# NeuroDAC_Output_v1.net
KiCad netlist of a schematic drawn in EAGLE
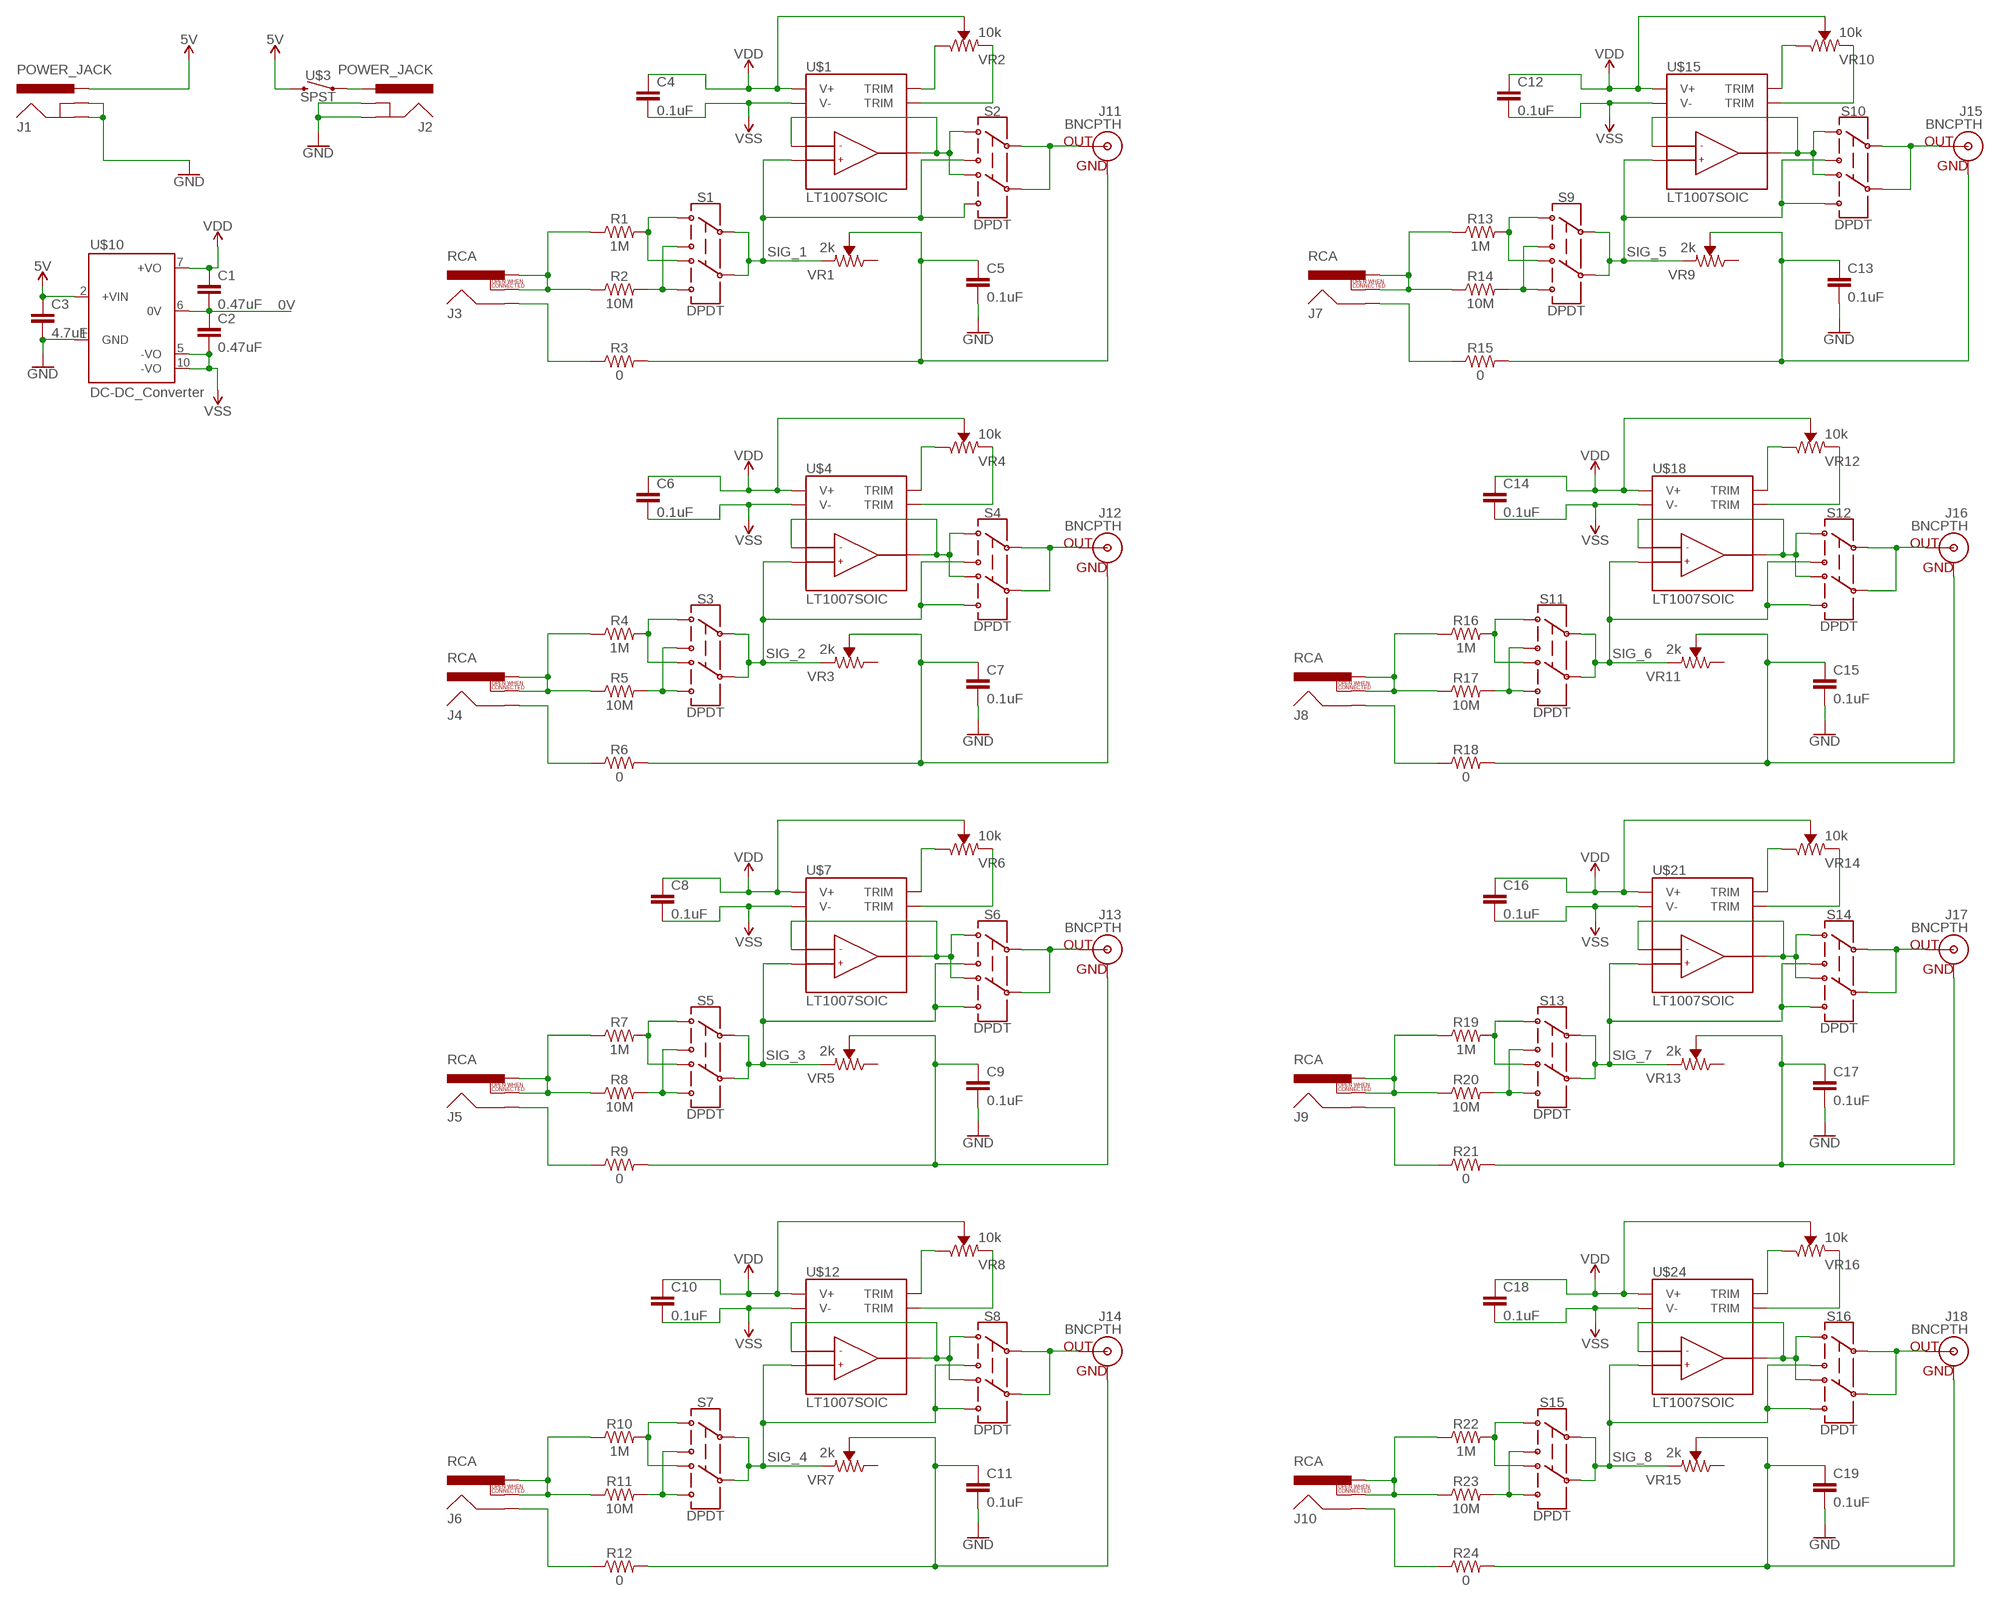
[diagram p0: schematic, sheet 1]

(export (version "E")
  (design (tool "Eeschema 10.0.6"))
  (components
    (comp (ref "C1")
      (value "0.47uF")
      (footprint "eagle-import:0603")
      (libsource (lib "eagle-import") (part "470NF-0603-25V-5%"))
    )
    (comp (ref "C2")
      (value "0.47uF")
      (footprint "eagle-import:0603")
      (libsource (lib "eagle-import") (part "470NF-0603-25V-5%"))
    )
    (comp (ref "C3")
      (value "4.7uF")
      (footprint "eagle-import:0805")
      (libsource (lib "eagle-import") (part "4.7UF-0805-25V-10%"))
    )
    (comp (ref "C4")
      (value "0.1uF")
      (footprint "eagle-import:0603")
      (libsource (lib "eagle-import") (part "0.1UF-0603-25V-5%"))
    )
    (comp (ref "C5")
      (value "0.1uF")
      (footprint "eagle-import:0603")
      (libsource (lib "eagle-import") (part "0.1UF-0603-25V-5%"))
    )
    (comp (ref "C6")
      (value "0.1uF")
      (footprint "eagle-import:0603")
      (libsource (lib "eagle-import") (part "0.1UF-0603-25V-5%"))
    )
    (comp (ref "C7")
      (value "0.1uF")
      (footprint "eagle-import:0603")
      (libsource (lib "eagle-import") (part "0.1UF-0603-25V-5%"))
    )
    (comp (ref "C8")
      (value "0.1uF")
      (footprint "eagle-import:0603")
      (libsource (lib "eagle-import") (part "0.1UF-0603-25V-5%"))
    )
    (comp (ref "C9")
      (value "0.1uF")
      (footprint "eagle-import:0603")
      (libsource (lib "eagle-import") (part "0.1UF-0603-25V-5%"))
    )
    (comp (ref "C10")
      (value "0.1uF")
      (footprint "eagle-import:0603")
      (libsource (lib "eagle-import") (part "0.1UF-0603-25V-5%"))
    )
    (comp (ref "C11")
      (value "0.1uF")
      (footprint "eagle-import:0603")
      (libsource (lib "eagle-import") (part "0.1UF-0603-25V-5%"))
    )
    (comp (ref "C12")
      (value "0.1uF")
      (footprint "eagle-import:0603")
      (libsource (lib "eagle-import") (part "0.1UF-0603-25V-5%"))
    )
    (comp (ref "C13")
      (value "0.1uF")
      (footprint "eagle-import:0603")
      (libsource (lib "eagle-import") (part "0.1UF-0603-25V-5%"))
    )
    (comp (ref "C14")
      (value "0.1uF")
      (footprint "eagle-import:0603")
      (libsource (lib "eagle-import") (part "0.1UF-0603-25V-5%"))
    )
    (comp (ref "C15")
      (value "0.1uF")
      (footprint "eagle-import:0603")
      (libsource (lib "eagle-import") (part "0.1UF-0603-25V-5%"))
    )
    (comp (ref "C16")
      (value "0.1uF")
      (footprint "eagle-import:0603")
      (libsource (lib "eagle-import") (part "0.1UF-0603-25V-5%"))
    )
    (comp (ref "C17")
      (value "0.1uF")
      (footprint "eagle-import:0603")
      (libsource (lib "eagle-import") (part "0.1UF-0603-25V-5%"))
    )
    (comp (ref "C18")
      (value "0.1uF")
      (footprint "eagle-import:0603")
      (libsource (lib "eagle-import") (part "0.1UF-0603-25V-5%"))
    )
    (comp (ref "C19")
      (value "0.1uF")
      (footprint "eagle-import:0603")
      (libsource (lib "eagle-import") (part "0.1UF-0603-25V-5%"))
    )
    (comp (ref "J1")
      (value "POWER_JACK")
      (footprint "eagle-import:POWER_JACK_PTH")
      (libsource (lib "eagle-import") (part "POWER_JACK"))
    )
    (comp (ref "J2")
      (value "POWER_JACK")
      (footprint "eagle-import:POWER_JACK_PTH")
      (libsource (lib "eagle-import") (part "POWER_JACK"))
    )
    (comp (ref "J3")
      (value "RCA")
      (footprint "eagle-import:RCA_LARGE_HOLE")
      (libsource (lib "eagle-import") (part "RCASWITCHCRAFT_LARGEHOLE"))
    )
    (comp (ref "J4")
      (value "RCA")
      (footprint "eagle-import:RCA_LARGE_HOLE")
      (libsource (lib "eagle-import") (part "RCASWITCHCRAFT_LARGEHOLE"))
    )
    (comp (ref "J5")
      (value "RCA")
      (footprint "eagle-import:RCA_LARGE_HOLE")
      (libsource (lib "eagle-import") (part "RCASWITCHCRAFT_LARGEHOLE"))
    )
    (comp (ref "J6")
      (value "RCA")
      (footprint "eagle-import:RCA_LARGE_HOLE")
      (libsource (lib "eagle-import") (part "RCASWITCHCRAFT_LARGEHOLE"))
    )
    (comp (ref "J7")
      (value "RCA")
      (footprint "eagle-import:RCA_LARGE_HOLE")
      (libsource (lib "eagle-import") (part "RCASWITCHCRAFT_LARGEHOLE"))
    )
    (comp (ref "J8")
      (value "RCA")
      (footprint "eagle-import:RCA_LARGE_HOLE")
      (libsource (lib "eagle-import") (part "RCASWITCHCRAFT_LARGEHOLE"))
    )
    (comp (ref "J9")
      (value "RCA")
      (footprint "eagle-import:RCA_LARGE_HOLE")
      (libsource (lib "eagle-import") (part "RCASWITCHCRAFT_LARGEHOLE"))
    )
    (comp (ref "J10")
      (value "RCA")
      (footprint "eagle-import:RCA_LARGE_HOLE")
      (libsource (lib "eagle-import") (part "RCASWITCHCRAFT_LARGEHOLE"))
    )
    (comp (ref "J11")
      (value "BNCPTH")
      (footprint "eagle-import:BNC")
      (libsource (lib "eagle-import") (part "BNCPTH"))
    )
    (comp (ref "J12")
      (value "BNCPTH")
      (footprint "eagle-import:BNC")
      (libsource (lib "eagle-import") (part "BNCPTH"))
    )
    (comp (ref "J13")
      (value "BNCPTH")
      (footprint "eagle-import:BNC")
      (libsource (lib "eagle-import") (part "BNCPTH"))
    )
    (comp (ref "J14")
      (value "BNCPTH")
      (footprint "eagle-import:BNC")
      (libsource (lib "eagle-import") (part "BNCPTH"))
    )
    (comp (ref "J15")
      (value "BNCPTH")
      (footprint "eagle-import:BNC")
      (libsource (lib "eagle-import") (part "BNCPTH"))
    )
    (comp (ref "J16")
      (value "BNCPTH")
      (footprint "eagle-import:BNC")
      (libsource (lib "eagle-import") (part "BNCPTH"))
    )
    (comp (ref "J17")
      (value "BNCPTH")
      (footprint "eagle-import:BNC")
      (libsource (lib "eagle-import") (part "BNCPTH"))
    )
    (comp (ref "J18")
      (value "BNCPTH")
      (footprint "eagle-import:BNC")
      (libsource (lib "eagle-import") (part "BNCPTH"))
    )
    (comp (ref "R1")
      (value "1M")
      (footprint "eagle-import:0603")
      (libsource (lib "eagle-import") (part "1MOHM-0603-1/4W-1%"))
    )
    (comp (ref "R2")
      (value "10M")
      (footprint "eagle-import:0603")
      (libsource (lib "eagle-import") (part "10MOHM-0603-1/4W-1%"))
    )
    (comp (ref "R3")
      (value "0")
      (footprint "eagle-import:0603")
      (libsource (lib "eagle-import") (part "0OHM-0603-1/4W"))
    )
    (comp (ref "R4")
      (value "1M")
      (footprint "eagle-import:0603")
      (libsource (lib "eagle-import") (part "1MOHM-0603-1/4W-1%"))
    )
    (comp (ref "R5")
      (value "10M")
      (footprint "eagle-import:0603")
      (libsource (lib "eagle-import") (part "10MOHM-0603-1/4W-1%"))
    )
    (comp (ref "R6")
      (value "0")
      (footprint "eagle-import:0603")
      (libsource (lib "eagle-import") (part "0OHM-0603-1/4W"))
    )
    (comp (ref "R7")
      (value "1M")
      (footprint "eagle-import:0603")
      (libsource (lib "eagle-import") (part "1MOHM-0603-1/4W-1%"))
    )
    (comp (ref "R8")
      (value "10M")
      (footprint "eagle-import:0603")
      (libsource (lib "eagle-import") (part "10MOHM-0603-1/4W-1%"))
    )
    (comp (ref "R9")
      (value "0")
      (footprint "eagle-import:0603")
      (libsource (lib "eagle-import") (part "0OHM-0603-1/4W"))
    )
    (comp (ref "R10")
      (value "1M")
      (footprint "eagle-import:0603")
      (libsource (lib "eagle-import") (part "1MOHM-0603-1/4W-1%"))
    )
    (comp (ref "R11")
      (value "10M")
      (footprint "eagle-import:0603")
      (libsource (lib "eagle-import") (part "10MOHM-0603-1/4W-1%"))
    )
    (comp (ref "R12")
      (value "0")
      (footprint "eagle-import:0603")
      (libsource (lib "eagle-import") (part "0OHM-0603-1/4W"))
    )
    (comp (ref "R13")
      (value "1M")
      (footprint "eagle-import:0603")
      (libsource (lib "eagle-import") (part "1MOHM-0603-1/4W-1%"))
    )
    (comp (ref "R14")
      (value "10M")
      (footprint "eagle-import:0603")
      (libsource (lib "eagle-import") (part "10MOHM-0603-1/4W-1%"))
    )
    (comp (ref "R15")
      (value "0")
      (footprint "eagle-import:0603")
      (libsource (lib "eagle-import") (part "0OHM-0603-1/4W"))
    )
    (comp (ref "R16")
      (value "1M")
      (footprint "eagle-import:0603")
      (libsource (lib "eagle-import") (part "1MOHM-0603-1/4W-1%"))
    )
    (comp (ref "R17")
      (value "10M")
      (footprint "eagle-import:0603")
      (libsource (lib "eagle-import") (part "10MOHM-0603-1/4W-1%"))
    )
    (comp (ref "R18")
      (value "0")
      (footprint "eagle-import:0603")
      (libsource (lib "eagle-import") (part "0OHM-0603-1/4W"))
    )
    (comp (ref "R19")
      (value "1M")
      (footprint "eagle-import:0603")
      (libsource (lib "eagle-import") (part "1MOHM-0603-1/4W-1%"))
    )
    (comp (ref "R20")
      (value "10M")
      (footprint "eagle-import:0603")
      (libsource (lib "eagle-import") (part "10MOHM-0603-1/4W-1%"))
    )
    (comp (ref "R21")
      (value "0")
      (footprint "eagle-import:0603")
      (libsource (lib "eagle-import") (part "0OHM-0603-1/4W"))
    )
    (comp (ref "R22")
      (value "1M")
      (footprint "eagle-import:0603")
      (libsource (lib "eagle-import") (part "1MOHM-0603-1/4W-1%"))
    )
    (comp (ref "R23")
      (value "10M")
      (footprint "eagle-import:0603")
      (libsource (lib "eagle-import") (part "10MOHM-0603-1/4W-1%"))
    )
    (comp (ref "R24")
      (value "0")
      (footprint "eagle-import:0603")
      (libsource (lib "eagle-import") (part "0OHM-0603-1/4W"))
    )
    (comp (ref "S1")
      (value "DPDT")
      (footprint "eagle-import:SWITCH_DPDT_JS202011SCQN")
      (libsource (lib "eagle-import") (part "SWITCH-DPDT-SMD-JS202011SCQN"))
    )
    (comp (ref "S2")
      (value "DPDT")
      (footprint "eagle-import:SWITCH_DPDT_JS202011SCQN")
      (libsource (lib "eagle-import") (part "SWITCH-DPDT-SMD-JS202011SCQN"))
    )
    (comp (ref "S3")
      (value "DPDT")
      (footprint "eagle-import:SWITCH_DPDT_JS202011SCQN")
      (libsource (lib "eagle-import") (part "SWITCH-DPDT-SMD-JS202011SCQN"))
    )
    (comp (ref "S4")
      (value "DPDT")
      (footprint "eagle-import:SWITCH_DPDT_JS202011SCQN")
      (libsource (lib "eagle-import") (part "SWITCH-DPDT-SMD-JS202011SCQN"))
    )
    (comp (ref "S5")
      (value "DPDT")
      (footprint "eagle-import:SWITCH_DPDT_JS202011SCQN")
      (libsource (lib "eagle-import") (part "SWITCH-DPDT-SMD-JS202011SCQN"))
    )
    (comp (ref "S6")
      (value "DPDT")
      (footprint "eagle-import:SWITCH_DPDT_JS202011SCQN")
      (libsource (lib "eagle-import") (part "SWITCH-DPDT-SMD-JS202011SCQN"))
    )
    (comp (ref "S7")
      (value "DPDT")
      (footprint "eagle-import:SWITCH_DPDT_JS202011SCQN")
      (libsource (lib "eagle-import") (part "SWITCH-DPDT-SMD-JS202011SCQN"))
    )
    (comp (ref "S8")
      (value "DPDT")
      (footprint "eagle-import:SWITCH_DPDT_JS202011SCQN")
      (libsource (lib "eagle-import") (part "SWITCH-DPDT-SMD-JS202011SCQN"))
    )
    (comp (ref "S9")
      (value "DPDT")
      (footprint "eagle-import:SWITCH_DPDT_JS202011SCQN")
      (libsource (lib "eagle-import") (part "SWITCH-DPDT-SMD-JS202011SCQN"))
    )
    (comp (ref "S10")
      (value "DPDT")
      (footprint "eagle-import:SWITCH_DPDT_JS202011SCQN")
      (libsource (lib "eagle-import") (part "SWITCH-DPDT-SMD-JS202011SCQN"))
    )
    (comp (ref "S11")
      (value "DPDT")
      (footprint "eagle-import:SWITCH_DPDT_JS202011SCQN")
      (libsource (lib "eagle-import") (part "SWITCH-DPDT-SMD-JS202011SCQN"))
    )
    (comp (ref "S12")
      (value "DPDT")
      (footprint "eagle-import:SWITCH_DPDT_JS202011SCQN")
      (libsource (lib "eagle-import") (part "SWITCH-DPDT-SMD-JS202011SCQN"))
    )
    (comp (ref "S13")
      (value "DPDT")
      (footprint "eagle-import:SWITCH_DPDT_JS202011SCQN")
      (libsource (lib "eagle-import") (part "SWITCH-DPDT-SMD-JS202011SCQN"))
    )
    (comp (ref "S14")
      (value "DPDT")
      (footprint "eagle-import:SWITCH_DPDT_JS202011SCQN")
      (libsource (lib "eagle-import") (part "SWITCH-DPDT-SMD-JS202011SCQN"))
    )
    (comp (ref "S15")
      (value "DPDT")
      (footprint "eagle-import:SWITCH_DPDT_JS202011SCQN")
      (libsource (lib "eagle-import") (part "SWITCH-DPDT-SMD-JS202011SCQN"))
    )
    (comp (ref "S16")
      (value "DPDT")
      (footprint "eagle-import:SWITCH_DPDT_JS202011SCQN")
      (libsource (lib "eagle-import") (part "SWITCH-DPDT-SMD-JS202011SCQN"))
    )
    (comp (ref "U$1")
      (value "LT1007SOIC")
      (footprint "eagle-import:S8")
      (libsource (lib "eagle-import") (part "LT1007SOIC"))
    )
    (comp (ref "U$3")
      (value "SPST")
      (footprint "eagle-import:SWITCH_SPST_L101011MS02Q")
      (libsource (lib "eagle-import") (part "SWITCH-SPST-L101011MS02Q"))
    )
    (comp (ref "U$4")
      (value "LT1007SOIC")
      (footprint "eagle-import:S8")
      (libsource (lib "eagle-import") (part "LT1007SOIC"))
    )
    (comp (ref "U$7")
      (value "LT1007SOIC")
      (footprint "eagle-import:S8")
      (libsource (lib "eagle-import") (part "LT1007SOIC"))
    )
    (comp (ref "U$10")
      (value "DC-DC_Converter")
      (footprint "eagle-import:VAT2-SMT")
      (libsource (lib "eagle-import") (part "DC-DC-CONVERTER_DUALOUT-VAT2-S5-D15-SMT"))
    )
    (comp (ref "U$12")
      (value "LT1007SOIC")
      (footprint "eagle-import:S8")
      (libsource (lib "eagle-import") (part "LT1007SOIC"))
    )
    (comp (ref "U$15")
      (value "LT1007SOIC")
      (footprint "eagle-import:S8")
      (libsource (lib "eagle-import") (part "LT1007SOIC"))
    )
    (comp (ref "U$18")
      (value "LT1007SOIC")
      (footprint "eagle-import:S8")
      (libsource (lib "eagle-import") (part "LT1007SOIC"))
    )
    (comp (ref "U$21")
      (value "LT1007SOIC")
      (footprint "eagle-import:S8")
      (libsource (lib "eagle-import") (part "LT1007SOIC"))
    )
    (comp (ref "U$24")
      (value "LT1007SOIC")
      (footprint "eagle-import:S8")
      (libsource (lib "eagle-import") (part "LT1007SOIC"))
    )
    (comp (ref "VR1")
      (value "2k")
      (footprint "eagle-import:TRIMPOT-SMD-ST4EB")
      (libsource (lib "eagle-import") (part "TRIMPOT-SMD-ST-4EB"))
    )
    (comp (ref "VR2")
      (value "10k")
      (footprint "eagle-import:TRIMPOT-SMD-ST4EB")
      (libsource (lib "eagle-import") (part "TRIMPOT-SMD-ST-4EB"))
    )
    (comp (ref "VR3")
      (value "2k")
      (footprint "eagle-import:TRIMPOT-SMD-ST4EB")
      (libsource (lib "eagle-import") (part "TRIMPOT-SMD-ST-4EB"))
    )
    (comp (ref "VR4")
      (value "10k")
      (footprint "eagle-import:TRIMPOT-SMD-ST4EB")
      (libsource (lib "eagle-import") (part "TRIMPOT-SMD-ST-4EB"))
    )
    (comp (ref "VR5")
      (value "2k")
      (footprint "eagle-import:TRIMPOT-SMD-ST4EB")
      (libsource (lib "eagle-import") (part "TRIMPOT-SMD-ST-4EB"))
    )
    (comp (ref "VR6")
      (value "10k")
      (footprint "eagle-import:TRIMPOT-SMD-ST4EB")
      (libsource (lib "eagle-import") (part "TRIMPOT-SMD-ST-4EB"))
    )
    (comp (ref "VR7")
      (value "2k")
      (footprint "eagle-import:TRIMPOT-SMD-ST4EB")
      (libsource (lib "eagle-import") (part "TRIMPOT-SMD-ST-4EB"))
    )
    (comp (ref "VR8")
      (value "10k")
      (footprint "eagle-import:TRIMPOT-SMD-ST4EB")
      (libsource (lib "eagle-import") (part "TRIMPOT-SMD-ST-4EB"))
    )
    (comp (ref "VR9")
      (value "2k")
      (footprint "eagle-import:TRIMPOT-SMD-ST4EB")
      (libsource (lib "eagle-import") (part "TRIMPOT-SMD-ST-4EB"))
    )
    (comp (ref "VR10")
      (value "10k")
      (footprint "eagle-import:TRIMPOT-SMD-ST4EB")
      (libsource (lib "eagle-import") (part "TRIMPOT-SMD-ST-4EB"))
    )
    (comp (ref "VR11")
      (value "2k")
      (footprint "eagle-import:TRIMPOT-SMD-ST4EB")
      (libsource (lib "eagle-import") (part "TRIMPOT-SMD-ST-4EB"))
    )
    (comp (ref "VR12")
      (value "10k")
      (footprint "eagle-import:TRIMPOT-SMD-ST4EB")
      (libsource (lib "eagle-import") (part "TRIMPOT-SMD-ST-4EB"))
    )
    (comp (ref "VR13")
      (value "2k")
      (footprint "eagle-import:TRIMPOT-SMD-ST4EB")
      (libsource (lib "eagle-import") (part "TRIMPOT-SMD-ST-4EB"))
    )
    (comp (ref "VR14")
      (value "10k")
      (footprint "eagle-import:TRIMPOT-SMD-ST4EB")
      (libsource (lib "eagle-import") (part "TRIMPOT-SMD-ST-4EB"))
    )
    (comp (ref "VR15")
      (value "2k")
      (footprint "eagle-import:TRIMPOT-SMD-ST4EB")
      (libsource (lib "eagle-import") (part "TRIMPOT-SMD-ST-4EB"))
    )
    (comp (ref "VR16")
      (value "10k")
      (footprint "eagle-import:TRIMPOT-SMD-ST4EB")
      (libsource (lib "eagle-import") (part "TRIMPOT-SMD-ST-4EB"))
    )
  )
  (nets
    (net (code "1") (name "/0V") (class "Default")
      (node (ref "C1") (pin "2") (pinfunction "2_2") (pintype "passive"))
      (node (ref "C11") (pin "1") (pinfunction "1_1") (pintype "passive"))
      (node (ref "C13") (pin "1") (pinfunction "1_1") (pintype "passive"))
      (node (ref "C15") (pin "1") (pinfunction "1_1") (pintype "passive"))
      (node (ref "C17") (pin "1") (pinfunction "1_1") (pintype "passive"))
      (node (ref "C19") (pin "1") (pinfunction "1_1") (pintype "passive"))
      (node (ref "C2") (pin "1") (pinfunction "1_1") (pintype "passive"))
      (node (ref "C5") (pin "1") (pinfunction "1_1") (pintype "passive"))
      (node (ref "C7") (pin "1") (pinfunction "1_1") (pintype "passive"))
      (node (ref "C9") (pin "1") (pinfunction "1_1") (pintype "passive"))
      (node (ref "J11") (pin "GND") (pinfunction "GND_GND") (pintype "bidirectional"))
      (node (ref "J12") (pin "GND") (pinfunction "GND_GND") (pintype "bidirectional"))
      (node (ref "J13") (pin "GND") (pinfunction "GND_GND") (pintype "bidirectional"))
      (node (ref "J14") (pin "GND") (pinfunction "GND_GND") (pintype "bidirectional"))
      (node (ref "J15") (pin "GND") (pinfunction "GND_GND") (pintype "bidirectional"))
      (node (ref "J16") (pin "GND") (pinfunction "GND_GND") (pintype "bidirectional"))
      (node (ref "J17") (pin "GND") (pinfunction "GND_GND") (pintype "bidirectional"))
      (node (ref "J18") (pin "GND") (pinfunction "GND_GND") (pintype "bidirectional"))
      (node (ref "R12") (pin "2") (pinfunction "2_2") (pintype "passive"))
      (node (ref "R15") (pin "2") (pinfunction "2_2") (pintype "passive"))
      (node (ref "R18") (pin "2") (pinfunction "2_2") (pintype "passive"))
      (node (ref "R21") (pin "2") (pinfunction "2_2") (pintype "passive"))
      (node (ref "R24") (pin "2") (pinfunction "2_2") (pintype "passive"))
      (node (ref "R3") (pin "2") (pinfunction "2_2") (pintype "passive"))
      (node (ref "R6") (pin "2") (pinfunction "2_2") (pintype "passive"))
      (node (ref "R9") (pin "2") (pinfunction "2_2") (pintype "passive"))
      (node (ref "U$10") (pin "6") (pinfunction "0V_6") (pintype "power_in"))
      (node (ref "VR1") (pin "2") (pinfunction "WIPER_2") (pintype "passive"))
      (node (ref "VR11") (pin "2") (pinfunction "WIPER_2") (pintype "passive"))
      (node (ref "VR13") (pin "2") (pinfunction "WIPER_2") (pintype "passive"))
      (node (ref "VR15") (pin "2") (pinfunction "WIPER_2") (pintype "passive"))
      (node (ref "VR3") (pin "2") (pinfunction "WIPER_2") (pintype "passive"))
      (node (ref "VR5") (pin "2") (pinfunction "WIPER_2") (pintype "passive"))
      (node (ref "VR7") (pin "2") (pinfunction "WIPER_2") (pintype "passive"))
      (node (ref "VR9") (pin "2") (pinfunction "WIPER_2") (pintype "passive"))
    )
    (net (code "2") (name "/SIG_1") (class "Default")
      (node (ref "S1") (pin "2") (pinfunction "2_2") (pintype "bidirectional"))
      (node (ref "S1") (pin "5") (pinfunction "5_5") (pintype "bidirectional"))
      (node (ref "S2") (pin "3") (pinfunction "3_3") (pintype "bidirectional"))
      (node (ref "S2") (pin "6") (pinfunction "6_6") (pintype "bidirectional"))
      (node (ref "U$1") (pin "3") (pinfunction "IN+_3") (pintype "input"))
      (node (ref "VR1") (pin "1") (pinfunction "CCW_1") (pintype "passive"))
    )
    (net (code "3") (name "/SIG_2") (class "Default")
      (node (ref "S3") (pin "2") (pinfunction "2_2") (pintype "bidirectional"))
      (node (ref "S3") (pin "5") (pinfunction "5_5") (pintype "bidirectional"))
      (node (ref "S4") (pin "3") (pinfunction "3_3") (pintype "bidirectional"))
      (node (ref "S4") (pin "6") (pinfunction "6_6") (pintype "bidirectional"))
      (node (ref "U$4") (pin "3") (pinfunction "IN+_3") (pintype "input"))
      (node (ref "VR3") (pin "1") (pinfunction "CCW_1") (pintype "passive"))
    )
    (net (code "4") (name "/SIG_3") (class "Default")
      (node (ref "S5") (pin "2") (pinfunction "2_2") (pintype "bidirectional"))
      (node (ref "S5") (pin "5") (pinfunction "5_5") (pintype "bidirectional"))
      (node (ref "S6") (pin "3") (pinfunction "3_3") (pintype "bidirectional"))
      (node (ref "S6") (pin "6") (pinfunction "6_6") (pintype "bidirectional"))
      (node (ref "U$7") (pin "3") (pinfunction "IN+_3") (pintype "input"))
      (node (ref "VR5") (pin "1") (pinfunction "CCW_1") (pintype "passive"))
    )
    (net (code "5") (name "/SIG_4") (class "Default")
      (node (ref "S7") (pin "2") (pinfunction "2_2") (pintype "bidirectional"))
      (node (ref "S7") (pin "5") (pinfunction "5_5") (pintype "bidirectional"))
      (node (ref "S8") (pin "3") (pinfunction "3_3") (pintype "bidirectional"))
      (node (ref "S8") (pin "6") (pinfunction "6_6") (pintype "bidirectional"))
      (node (ref "U$12") (pin "3") (pinfunction "IN+_3") (pintype "input"))
      (node (ref "VR7") (pin "1") (pinfunction "CCW_1") (pintype "passive"))
    )
    (net (code "6") (name "/SIG_5") (class "Default")
      (node (ref "S10") (pin "3") (pinfunction "3_3") (pintype "bidirectional"))
      (node (ref "S10") (pin "6") (pinfunction "6_6") (pintype "bidirectional"))
      (node (ref "S9") (pin "2") (pinfunction "2_2") (pintype "bidirectional"))
      (node (ref "S9") (pin "5") (pinfunction "5_5") (pintype "bidirectional"))
      (node (ref "U$15") (pin "3") (pinfunction "IN+_3") (pintype "input"))
      (node (ref "VR9") (pin "1") (pinfunction "CCW_1") (pintype "passive"))
    )
    (net (code "7") (name "/SIG_6") (class "Default")
      (node (ref "S11") (pin "2") (pinfunction "2_2") (pintype "bidirectional"))
      (node (ref "S11") (pin "5") (pinfunction "5_5") (pintype "bidirectional"))
      (node (ref "S12") (pin "3") (pinfunction "3_3") (pintype "bidirectional"))
      (node (ref "S12") (pin "6") (pinfunction "6_6") (pintype "bidirectional"))
      (node (ref "U$18") (pin "3") (pinfunction "IN+_3") (pintype "input"))
      (node (ref "VR11") (pin "1") (pinfunction "CCW_1") (pintype "passive"))
    )
    (net (code "8") (name "/SIG_7") (class "Default")
      (node (ref "S13") (pin "2") (pinfunction "2_2") (pintype "bidirectional"))
      (node (ref "S13") (pin "5") (pinfunction "5_5") (pintype "bidirectional"))
      (node (ref "S14") (pin "3") (pinfunction "3_3") (pintype "bidirectional"))
      (node (ref "S14") (pin "6") (pinfunction "6_6") (pintype "bidirectional"))
      (node (ref "U$21") (pin "3") (pinfunction "IN+_3") (pintype "input"))
      (node (ref "VR13") (pin "1") (pinfunction "CCW_1") (pintype "passive"))
    )
    (net (code "9") (name "/SIG_8") (class "Default")
      (node (ref "S15") (pin "2") (pinfunction "2_2") (pintype "bidirectional"))
      (node (ref "S15") (pin "5") (pinfunction "5_5") (pintype "bidirectional"))
      (node (ref "S16") (pin "3") (pinfunction "3_3") (pintype "bidirectional"))
      (node (ref "S16") (pin "6") (pinfunction "6_6") (pintype "bidirectional"))
      (node (ref "U$24") (pin "3") (pinfunction "IN+_3") (pintype "input"))
      (node (ref "VR15") (pin "1") (pinfunction "CCW_1") (pintype "passive"))
    )
    (net (code "10") (name "5V") (class "Default")
      (node (ref "C3") (pin "1") (pinfunction "1_1") (pintype "passive"))
      (node (ref "J1") (pin "PWR") (pinfunction "PWR_PWR") (pintype "bidirectional"))
      (node (ref "U$10") (pin "2") (pinfunction "+VIN_2") (pintype "power_in"))
      (node (ref "U$3") (pin "2") (pinfunction "2_2") (pintype "passive"))
    )
    (net (code "11") (name "GND") (class "Default")
      (node (ref "C11") (pin "2") (pinfunction "2_2") (pintype "passive"))
      (node (ref "C13") (pin "2") (pinfunction "2_2") (pintype "passive"))
      (node (ref "C15") (pin "2") (pinfunction "2_2") (pintype "passive"))
      (node (ref "C17") (pin "2") (pinfunction "2_2") (pintype "passive"))
      (node (ref "C19") (pin "2") (pinfunction "2_2") (pintype "passive"))
      (node (ref "C3") (pin "2") (pinfunction "2_2") (pintype "passive"))
      (node (ref "C5") (pin "2") (pinfunction "2_2") (pintype "passive"))
      (node (ref "C7") (pin "2") (pinfunction "2_2") (pintype "passive"))
      (node (ref "C9") (pin "2") (pinfunction "2_2") (pintype "passive"))
      (node (ref "J1") (pin "GND") (pinfunction "GND_GND") (pintype "bidirectional"))
      (node (ref "J1") (pin "GNDBREAK") (pinfunction "GNDBREAK_GNDBREAK") (pintype "bidirectional"))
      (node (ref "J2") (pin "GND") (pinfunction "GND_GND") (pintype "bidirectional"))
      (node (ref "J2") (pin "GNDBREAK") (pinfunction "GNDBREAK_GNDBREAK") (pintype "bidirectional"))
      (node (ref "U$10") (pin "1") (pinfunction "GND_1") (pintype "power_in"))
    )
    (net (code "12") (name "Net-(J2-PadPWR)") (class "Default")
      (node (ref "J2") (pin "PWR") (pinfunction "PWR_PWR") (pintype "bidirectional"))
      (node (ref "U$3") (pin "1") (pinfunction "1_1") (pintype "passive"))
    )
    (net (code "13") (name "Net-(J3-PadPIN)") (class "Default")
      (node (ref "J3") (pin "PIN") (pinfunction "PIN_PIN") (pintype "bidirectional"))
      (node (ref "J3") (pin "SWITCH") (pinfunction "SWITCH_SWITCH") (pintype "bidirectional"))
      (node (ref "R1") (pin "1") (pinfunction "1_1") (pintype "passive"))
      (node (ref "R2") (pin "1") (pinfunction "1_1") (pintype "passive"))
    )
    (net (code "14") (name "Net-(J3-PadSHELL)") (class "Default")
      (node (ref "J3") (pin "SHELL") (pinfunction "SHELL_SHELL") (pintype "bidirectional"))
      (node (ref "R3") (pin "1") (pinfunction "1_1") (pintype "passive"))
    )
    (net (code "15") (name "Net-(J4-PadPIN)") (class "Default")
      (node (ref "J4") (pin "PIN") (pinfunction "PIN_PIN") (pintype "bidirectional"))
      (node (ref "J4") (pin "SWITCH") (pinfunction "SWITCH_SWITCH") (pintype "bidirectional"))
      (node (ref "R4") (pin "1") (pinfunction "1_1") (pintype "passive"))
      (node (ref "R5") (pin "1") (pinfunction "1_1") (pintype "passive"))
    )
    (net (code "16") (name "Net-(J4-PadSHELL)") (class "Default")
      (node (ref "J4") (pin "SHELL") (pinfunction "SHELL_SHELL") (pintype "bidirectional"))
      (node (ref "R6") (pin "1") (pinfunction "1_1") (pintype "passive"))
    )
    (net (code "17") (name "Net-(J5-PadPIN)") (class "Default")
      (node (ref "J5") (pin "PIN") (pinfunction "PIN_PIN") (pintype "bidirectional"))
      (node (ref "J5") (pin "SWITCH") (pinfunction "SWITCH_SWITCH") (pintype "bidirectional"))
      (node (ref "R7") (pin "1") (pinfunction "1_1") (pintype "passive"))
      (node (ref "R8") (pin "1") (pinfunction "1_1") (pintype "passive"))
    )
    (net (code "18") (name "Net-(J5-PadSHELL)") (class "Default")
      (node (ref "J5") (pin "SHELL") (pinfunction "SHELL_SHELL") (pintype "bidirectional"))
      (node (ref "R9") (pin "1") (pinfunction "1_1") (pintype "passive"))
    )
    (net (code "19") (name "Net-(J6-PadPIN)") (class "Default")
      (node (ref "J6") (pin "PIN") (pinfunction "PIN_PIN") (pintype "bidirectional"))
      (node (ref "J6") (pin "SWITCH") (pinfunction "SWITCH_SWITCH") (pintype "bidirectional"))
      (node (ref "R10") (pin "1") (pinfunction "1_1") (pintype "passive"))
      (node (ref "R11") (pin "1") (pinfunction "1_1") (pintype "passive"))
    )
    (net (code "20") (name "Net-(J6-PadSHELL)") (class "Default")
      (node (ref "J6") (pin "SHELL") (pinfunction "SHELL_SHELL") (pintype "bidirectional"))
      (node (ref "R12") (pin "1") (pinfunction "1_1") (pintype "passive"))
    )
    (net (code "21") (name "Net-(J7-PadPIN)") (class "Default")
      (node (ref "J7") (pin "PIN") (pinfunction "PIN_PIN") (pintype "bidirectional"))
      (node (ref "J7") (pin "SWITCH") (pinfunction "SWITCH_SWITCH") (pintype "bidirectional"))
      (node (ref "R13") (pin "1") (pinfunction "1_1") (pintype "passive"))
      (node (ref "R14") (pin "1") (pinfunction "1_1") (pintype "passive"))
    )
    (net (code "22") (name "Net-(J7-PadSHELL)") (class "Default")
      (node (ref "J7") (pin "SHELL") (pinfunction "SHELL_SHELL") (pintype "bidirectional"))
      (node (ref "R15") (pin "1") (pinfunction "1_1") (pintype "passive"))
    )
    (net (code "23") (name "Net-(J8-PadPIN)") (class "Default")
      (node (ref "J8") (pin "PIN") (pinfunction "PIN_PIN") (pintype "bidirectional"))
      (node (ref "J8") (pin "SWITCH") (pinfunction "SWITCH_SWITCH") (pintype "bidirectional"))
      (node (ref "R16") (pin "1") (pinfunction "1_1") (pintype "passive"))
      (node (ref "R17") (pin "1") (pinfunction "1_1") (pintype "passive"))
    )
    (net (code "24") (name "Net-(J8-PadSHELL)") (class "Default")
      (node (ref "J8") (pin "SHELL") (pinfunction "SHELL_SHELL") (pintype "bidirectional"))
      (node (ref "R18") (pin "1") (pinfunction "1_1") (pintype "passive"))
    )
    (net (code "25") (name "Net-(J9-PadPIN)") (class "Default")
      (node (ref "J9") (pin "PIN") (pinfunction "PIN_PIN") (pintype "bidirectional"))
      (node (ref "J9") (pin "SWITCH") (pinfunction "SWITCH_SWITCH") (pintype "bidirectional"))
      (node (ref "R19") (pin "1") (pinfunction "1_1") (pintype "passive"))
      (node (ref "R20") (pin "1") (pinfunction "1_1") (pintype "passive"))
    )
    (net (code "26") (name "Net-(J9-PadSHELL)") (class "Default")
      (node (ref "J9") (pin "SHELL") (pinfunction "SHELL_SHELL") (pintype "bidirectional"))
      (node (ref "R21") (pin "1") (pinfunction "1_1") (pintype "passive"))
    )
    (net (code "27") (name "Net-(J10-PadPIN)") (class "Default")
      (node (ref "J10") (pin "PIN") (pinfunction "PIN_PIN") (pintype "bidirectional"))
      (node (ref "J10") (pin "SWITCH") (pinfunction "SWITCH_SWITCH") (pintype "bidirectional"))
      (node (ref "R22") (pin "1") (pinfunction "1_1") (pintype "passive"))
      (node (ref "R23") (pin "1") (pinfunction "1_1") (pintype "passive"))
    )
    (net (code "28") (name "Net-(J10-PadSHELL)") (class "Default")
      (node (ref "J10") (pin "SHELL") (pinfunction "SHELL_SHELL") (pintype "bidirectional"))
      (node (ref "R24") (pin "1") (pinfunction "1_1") (pintype "passive"))
    )
    (net (code "29") (name "Net-(J11-OUT)") (class "Default")
      (node (ref "J11") (pin "S") (pinfunction "OUT_S") (pintype "bidirectional"))
      (node (ref "S2") (pin "2") (pinfunction "2_2") (pintype "bidirectional"))
      (node (ref "S2") (pin "5") (pinfunction "5_5") (pintype "bidirectional"))
    )
    (net (code "30") (name "Net-(J12-OUT)") (class "Default")
      (node (ref "J12") (pin "S") (pinfunction "OUT_S") (pintype "bidirectional"))
      (node (ref "S4") (pin "2") (pinfunction "2_2") (pintype "bidirectional"))
      (node (ref "S4") (pin "5") (pinfunction "5_5") (pintype "bidirectional"))
    )
    (net (code "31") (name "Net-(J13-OUT)") (class "Default")
      (node (ref "J13") (pin "S") (pinfunction "OUT_S") (pintype "bidirectional"))
      (node (ref "S6") (pin "2") (pinfunction "2_2") (pintype "bidirectional"))
      (node (ref "S6") (pin "5") (pinfunction "5_5") (pintype "bidirectional"))
    )
    (net (code "32") (name "Net-(J14-OUT)") (class "Default")
      (node (ref "J14") (pin "S") (pinfunction "OUT_S") (pintype "bidirectional"))
      (node (ref "S8") (pin "2") (pinfunction "2_2") (pintype "bidirectional"))
      (node (ref "S8") (pin "5") (pinfunction "5_5") (pintype "bidirectional"))
    )
    (net (code "33") (name "Net-(J15-OUT)") (class "Default")
      (node (ref "J15") (pin "S") (pinfunction "OUT_S") (pintype "bidirectional"))
      (node (ref "S10") (pin "2") (pinfunction "2_2") (pintype "bidirectional"))
      (node (ref "S10") (pin "5") (pinfunction "5_5") (pintype "bidirectional"))
    )
    (net (code "34") (name "Net-(J16-OUT)") (class "Default")
      (node (ref "J16") (pin "S") (pinfunction "OUT_S") (pintype "bidirectional"))
      (node (ref "S12") (pin "2") (pinfunction "2_2") (pintype "bidirectional"))
      (node (ref "S12") (pin "5") (pinfunction "5_5") (pintype "bidirectional"))
    )
    (net (code "35") (name "Net-(J17-OUT)") (class "Default")
      (node (ref "J17") (pin "S") (pinfunction "OUT_S") (pintype "bidirectional"))
      (node (ref "S14") (pin "2") (pinfunction "2_2") (pintype "bidirectional"))
      (node (ref "S14") (pin "5") (pinfunction "5_5") (pintype "bidirectional"))
    )
    (net (code "36") (name "Net-(J18-OUT)") (class "Default")
      (node (ref "J18") (pin "S") (pinfunction "OUT_S") (pintype "bidirectional"))
      (node (ref "S16") (pin "2") (pinfunction "2_2") (pintype "bidirectional"))
      (node (ref "S16") (pin "5") (pinfunction "5_5") (pintype "bidirectional"))
    )
    (net (code "37") (name "Net-(R1-Pad2)") (class "Default")
      (node (ref "R1") (pin "2") (pinfunction "2_2") (pintype "passive"))
      (node (ref "S1") (pin "1") (pinfunction "1_1") (pintype "bidirectional"))
      (node (ref "S1") (pin "4") (pinfunction "4_4") (pintype "bidirectional"))
    )
    (net (code "38") (name "Net-(R2-Pad2)") (class "Default")
      (node (ref "R2") (pin "2") (pinfunction "2_2") (pintype "passive"))
      (node (ref "S1") (pin "3") (pinfunction "3_3") (pintype "bidirectional"))
      (node (ref "S1") (pin "6") (pinfunction "6_6") (pintype "bidirectional"))
    )
    (net (code "39") (name "Net-(R4-Pad2)") (class "Default")
      (node (ref "R4") (pin "2") (pinfunction "2_2") (pintype "passive"))
      (node (ref "S3") (pin "1") (pinfunction "1_1") (pintype "bidirectional"))
      (node (ref "S3") (pin "4") (pinfunction "4_4") (pintype "bidirectional"))
    )
    (net (code "40") (name "Net-(R5-Pad2)") (class "Default")
      (node (ref "R5") (pin "2") (pinfunction "2_2") (pintype "passive"))
      (node (ref "S3") (pin "3") (pinfunction "3_3") (pintype "bidirectional"))
      (node (ref "S3") (pin "6") (pinfunction "6_6") (pintype "bidirectional"))
    )
    (net (code "41") (name "Net-(R7-Pad2)") (class "Default")
      (node (ref "R7") (pin "2") (pinfunction "2_2") (pintype "passive"))
      (node (ref "S5") (pin "1") (pinfunction "1_1") (pintype "bidirectional"))
      (node (ref "S5") (pin "4") (pinfunction "4_4") (pintype "bidirectional"))
    )
    (net (code "42") (name "Net-(R8-Pad2)") (class "Default")
      (node (ref "R8") (pin "2") (pinfunction "2_2") (pintype "passive"))
      (node (ref "S5") (pin "3") (pinfunction "3_3") (pintype "bidirectional"))
      (node (ref "S5") (pin "6") (pinfunction "6_6") (pintype "bidirectional"))
    )
    (net (code "43") (name "Net-(R10-Pad2)") (class "Default")
      (node (ref "R10") (pin "2") (pinfunction "2_2") (pintype "passive"))
      (node (ref "S7") (pin "1") (pinfunction "1_1") (pintype "bidirectional"))
      (node (ref "S7") (pin "4") (pinfunction "4_4") (pintype "bidirectional"))
    )
    (net (code "44") (name "Net-(R11-Pad2)") (class "Default")
      (node (ref "R11") (pin "2") (pinfunction "2_2") (pintype "passive"))
      (node (ref "S7") (pin "3") (pinfunction "3_3") (pintype "bidirectional"))
      (node (ref "S7") (pin "6") (pinfunction "6_6") (pintype "bidirectional"))
    )
    (net (code "45") (name "Net-(R13-Pad2)") (class "Default")
      (node (ref "R13") (pin "2") (pinfunction "2_2") (pintype "passive"))
      (node (ref "S9") (pin "1") (pinfunction "1_1") (pintype "bidirectional"))
      (node (ref "S9") (pin "4") (pinfunction "4_4") (pintype "bidirectional"))
    )
    (net (code "46") (name "Net-(R14-Pad2)") (class "Default")
      (node (ref "R14") (pin "2") (pinfunction "2_2") (pintype "passive"))
      (node (ref "S9") (pin "3") (pinfunction "3_3") (pintype "bidirectional"))
      (node (ref "S9") (pin "6") (pinfunction "6_6") (pintype "bidirectional"))
    )
    (net (code "47") (name "Net-(R16-Pad2)") (class "Default")
      (node (ref "R16") (pin "2") (pinfunction "2_2") (pintype "passive"))
      (node (ref "S11") (pin "1") (pinfunction "1_1") (pintype "bidirectional"))
      (node (ref "S11") (pin "4") (pinfunction "4_4") (pintype "bidirectional"))
    )
    (net (code "48") (name "Net-(R17-Pad2)") (class "Default")
      (node (ref "R17") (pin "2") (pinfunction "2_2") (pintype "passive"))
      (node (ref "S11") (pin "3") (pinfunction "3_3") (pintype "bidirectional"))
      (node (ref "S11") (pin "6") (pinfunction "6_6") (pintype "bidirectional"))
    )
    (net (code "49") (name "Net-(R19-Pad2)") (class "Default")
      (node (ref "R19") (pin "2") (pinfunction "2_2") (pintype "passive"))
      (node (ref "S13") (pin "1") (pinfunction "1_1") (pintype "bidirectional"))
      (node (ref "S13") (pin "4") (pinfunction "4_4") (pintype "bidirectional"))
    )
    (net (code "50") (name "Net-(R20-Pad2)") (class "Default")
      (node (ref "R20") (pin "2") (pinfunction "2_2") (pintype "passive"))
      (node (ref "S13") (pin "3") (pinfunction "3_3") (pintype "bidirectional"))
      (node (ref "S13") (pin "6") (pinfunction "6_6") (pintype "bidirectional"))
    )
    (net (code "51") (name "Net-(R22-Pad2)") (class "Default")
      (node (ref "R22") (pin "2") (pinfunction "2_2") (pintype "passive"))
      (node (ref "S15") (pin "1") (pinfunction "1_1") (pintype "bidirectional"))
      (node (ref "S15") (pin "4") (pinfunction "4_4") (pintype "bidirectional"))
    )
    (net (code "52") (name "Net-(R23-Pad2)") (class "Default")
      (node (ref "R23") (pin "2") (pinfunction "2_2") (pintype "passive"))
      (node (ref "S15") (pin "3") (pinfunction "3_3") (pintype "bidirectional"))
      (node (ref "S15") (pin "6") (pinfunction "6_6") (pintype "bidirectional"))
    )
    (net (code "53") (name "Net-(U$1-IN-)") (class "Default")
      (node (ref "S2") (pin "1") (pinfunction "1_1") (pintype "bidirectional"))
      (node (ref "S2") (pin "4") (pinfunction "4_4") (pintype "bidirectional"))
      (node (ref "U$1") (pin "2") (pinfunction "IN-_2") (pintype "input"))
      (node (ref "U$1") (pin "6") (pinfunction "OUT_6") (pintype "output"))
    )
    (net (code "54") (name "Net-(U$4-IN-)") (class "Default")
      (node (ref "S4") (pin "1") (pinfunction "1_1") (pintype "bidirectional"))
      (node (ref "S4") (pin "4") (pinfunction "4_4") (pintype "bidirectional"))
      (node (ref "U$4") (pin "2") (pinfunction "IN-_2") (pintype "input"))
      (node (ref "U$4") (pin "6") (pinfunction "OUT_6") (pintype "output"))
    )
    (net (code "55") (name "Net-(U$7-IN-)") (class "Default")
      (node (ref "S6") (pin "1") (pinfunction "1_1") (pintype "bidirectional"))
      (node (ref "S6") (pin "4") (pinfunction "4_4") (pintype "bidirectional"))
      (node (ref "U$7") (pin "2") (pinfunction "IN-_2") (pintype "input"))
      (node (ref "U$7") (pin "6") (pinfunction "OUT_6") (pintype "output"))
    )
    (net (code "56") (name "Net-(U$12-IN-)") (class "Default")
      (node (ref "S8") (pin "1") (pinfunction "1_1") (pintype "bidirectional"))
      (node (ref "S8") (pin "4") (pinfunction "4_4") (pintype "bidirectional"))
      (node (ref "U$12") (pin "2") (pinfunction "IN-_2") (pintype "input"))
      (node (ref "U$12") (pin "6") (pinfunction "OUT_6") (pintype "output"))
    )
    (net (code "57") (name "Net-(U$15-IN-)") (class "Default")
      (node (ref "S10") (pin "1") (pinfunction "1_1") (pintype "bidirectional"))
      (node (ref "S10") (pin "4") (pinfunction "4_4") (pintype "bidirectional"))
      (node (ref "U$15") (pin "2") (pinfunction "IN-_2") (pintype "input"))
      (node (ref "U$15") (pin "6") (pinfunction "OUT_6") (pintype "output"))
    )
    (net (code "58") (name "Net-(U$18-IN-)") (class "Default")
      (node (ref "S12") (pin "1") (pinfunction "1_1") (pintype "bidirectional"))
      (node (ref "S12") (pin "4") (pinfunction "4_4") (pintype "bidirectional"))
      (node (ref "U$18") (pin "2") (pinfunction "IN-_2") (pintype "input"))
      (node (ref "U$18") (pin "6") (pinfunction "OUT_6") (pintype "output"))
    )
    (net (code "59") (name "Net-(U$21-IN-)") (class "Default")
      (node (ref "S14") (pin "1") (pinfunction "1_1") (pintype "bidirectional"))
      (node (ref "S14") (pin "4") (pinfunction "4_4") (pintype "bidirectional"))
      (node (ref "U$21") (pin "2") (pinfunction "IN-_2") (pintype "input"))
      (node (ref "U$21") (pin "6") (pinfunction "OUT_6") (pintype "output"))
    )
    (net (code "60") (name "Net-(U$24-IN-)") (class "Default")
      (node (ref "S16") (pin "1") (pinfunction "1_1") (pintype "bidirectional"))
      (node (ref "S16") (pin "4") (pinfunction "4_4") (pintype "bidirectional"))
      (node (ref "U$24") (pin "2") (pinfunction "IN-_2") (pintype "input"))
      (node (ref "U$24") (pin "6") (pinfunction "OUT_6") (pintype "output"))
    )
    (net (code "61") (name "Net-(VR2-CCW)") (class "Default")
      (node (ref "U$1") (pin "8") (pinfunction "TRIM_8") (pintype "bidirectional"))
      (node (ref "VR2") (pin "1") (pinfunction "CCW_1") (pintype "passive"))
    )
    (net (code "62") (name "Net-(VR2-CW)") (class "Default")
      (node (ref "U$1") (pin "1") (pinfunction "TRIM_1") (pintype "bidirectional"))
      (node (ref "VR2") (pin "3") (pinfunction "CW_3") (pintype "passive"))
    )
    (net (code "63") (name "Net-(VR4-CCW)") (class "Default")
      (node (ref "U$4") (pin "8") (pinfunction "TRIM_8") (pintype "bidirectional"))
      (node (ref "VR4") (pin "1") (pinfunction "CCW_1") (pintype "passive"))
    )
    (net (code "64") (name "Net-(VR4-CW)") (class "Default")
      (node (ref "U$4") (pin "1") (pinfunction "TRIM_1") (pintype "bidirectional"))
      (node (ref "VR4") (pin "3") (pinfunction "CW_3") (pintype "passive"))
    )
    (net (code "65") (name "Net-(VR6-CCW)") (class "Default")
      (node (ref "U$7") (pin "8") (pinfunction "TRIM_8") (pintype "bidirectional"))
      (node (ref "VR6") (pin "1") (pinfunction "CCW_1") (pintype "passive"))
    )
    (net (code "66") (name "Net-(VR6-CW)") (class "Default")
      (node (ref "U$7") (pin "1") (pinfunction "TRIM_1") (pintype "bidirectional"))
      (node (ref "VR6") (pin "3") (pinfunction "CW_3") (pintype "passive"))
    )
    (net (code "67") (name "Net-(VR8-CCW)") (class "Default")
      (node (ref "U$12") (pin "8") (pinfunction "TRIM_8") (pintype "bidirectional"))
      (node (ref "VR8") (pin "1") (pinfunction "CCW_1") (pintype "passive"))
    )
    (net (code "68") (name "Net-(VR8-CW)") (class "Default")
      (node (ref "U$12") (pin "1") (pinfunction "TRIM_1") (pintype "bidirectional"))
      (node (ref "VR8") (pin "3") (pinfunction "CW_3") (pintype "passive"))
    )
    (net (code "69") (name "Net-(VR10-CCW)") (class "Default")
      (node (ref "U$15") (pin "8") (pinfunction "TRIM_8") (pintype "bidirectional"))
      (node (ref "VR10") (pin "1") (pinfunction "CCW_1") (pintype "passive"))
    )
    (net (code "70") (name "Net-(VR10-CW)") (class "Default")
      (node (ref "U$15") (pin "1") (pinfunction "TRIM_1") (pintype "bidirectional"))
      (node (ref "VR10") (pin "3") (pinfunction "CW_3") (pintype "passive"))
    )
    (net (code "71") (name "Net-(VR12-CCW)") (class "Default")
      (node (ref "U$18") (pin "8") (pinfunction "TRIM_8") (pintype "bidirectional"))
      (node (ref "VR12") (pin "1") (pinfunction "CCW_1") (pintype "passive"))
    )
    (net (code "72") (name "Net-(VR12-CW)") (class "Default")
      (node (ref "U$18") (pin "1") (pinfunction "TRIM_1") (pintype "bidirectional"))
      (node (ref "VR12") (pin "3") (pinfunction "CW_3") (pintype "passive"))
    )
    (net (code "73") (name "Net-(VR14-CCW)") (class "Default")
      (node (ref "U$21") (pin "8") (pinfunction "TRIM_8") (pintype "bidirectional"))
      (node (ref "VR14") (pin "1") (pinfunction "CCW_1") (pintype "passive"))
    )
    (net (code "74") (name "Net-(VR14-CW)") (class "Default")
      (node (ref "U$21") (pin "1") (pinfunction "TRIM_1") (pintype "bidirectional"))
      (node (ref "VR14") (pin "3") (pinfunction "CW_3") (pintype "passive"))
    )
    (net (code "75") (name "Net-(VR16-CCW)") (class "Default")
      (node (ref "U$24") (pin "8") (pinfunction "TRIM_8") (pintype "bidirectional"))
      (node (ref "VR16") (pin "1") (pinfunction "CCW_1") (pintype "passive"))
    )
    (net (code "76") (name "Net-(VR16-CW)") (class "Default")
      (node (ref "U$24") (pin "1") (pinfunction "TRIM_1") (pintype "bidirectional"))
      (node (ref "VR16") (pin "3") (pinfunction "CW_3") (pintype "passive"))
    )
    (net (code "77") (name "VDD") (class "Default")
      (node (ref "C1") (pin "1") (pinfunction "1_1") (pintype "passive"))
      (node (ref "C10") (pin "1") (pinfunction "1_1") (pintype "passive"))
      (node (ref "C12") (pin "1") (pinfunction "1_1") (pintype "passive"))
      (node (ref "C14") (pin "1") (pinfunction "1_1") (pintype "passive"))
      (node (ref "C16") (pin "1") (pinfunction "1_1") (pintype "passive"))
      (node (ref "C18") (pin "1") (pinfunction "1_1") (pintype "passive"))
      (node (ref "C4") (pin "1") (pinfunction "1_1") (pintype "passive"))
      (node (ref "C6") (pin "1") (pinfunction "1_1") (pintype "passive"))
      (node (ref "C8") (pin "1") (pinfunction "1_1") (pintype "passive"))
      (node (ref "U$1") (pin "7") (pinfunction "V+_7") (pintype "power_in"))
      (node (ref "U$10") (pin "7") (pinfunction "+VO_7") (pintype "power_in"))
      (node (ref "U$12") (pin "7") (pinfunction "V+_7") (pintype "power_in"))
      (node (ref "U$15") (pin "7") (pinfunction "V+_7") (pintype "power_in"))
      (node (ref "U$18") (pin "7") (pinfunction "V+_7") (pintype "power_in"))
      (node (ref "U$21") (pin "7") (pinfunction "V+_7") (pintype "power_in"))
      (node (ref "U$24") (pin "7") (pinfunction "V+_7") (pintype "power_in"))
      (node (ref "U$4") (pin "7") (pinfunction "V+_7") (pintype "power_in"))
      (node (ref "U$7") (pin "7") (pinfunction "V+_7") (pintype "power_in"))
      (node (ref "VR10") (pin "2") (pinfunction "WIPER_2") (pintype "passive"))
      (node (ref "VR12") (pin "2") (pinfunction "WIPER_2") (pintype "passive"))
      (node (ref "VR14") (pin "2") (pinfunction "WIPER_2") (pintype "passive"))
      (node (ref "VR16") (pin "2") (pinfunction "WIPER_2") (pintype "passive"))
      (node (ref "VR2") (pin "2") (pinfunction "WIPER_2") (pintype "passive"))
      (node (ref "VR4") (pin "2") (pinfunction "WIPER_2") (pintype "passive"))
      (node (ref "VR6") (pin "2") (pinfunction "WIPER_2") (pintype "passive"))
      (node (ref "VR8") (pin "2") (pinfunction "WIPER_2") (pintype "passive"))
    )
    (net (code "78") (name "VSS") (class "Default")
      (node (ref "C10") (pin "2") (pinfunction "2_2") (pintype "passive"))
      (node (ref "C12") (pin "2") (pinfunction "2_2") (pintype "passive"))
      (node (ref "C14") (pin "2") (pinfunction "2_2") (pintype "passive"))
      (node (ref "C16") (pin "2") (pinfunction "2_2") (pintype "passive"))
      (node (ref "C18") (pin "2") (pinfunction "2_2") (pintype "passive"))
      (node (ref "C2") (pin "2") (pinfunction "2_2") (pintype "passive"))
      (node (ref "C4") (pin "2") (pinfunction "2_2") (pintype "passive"))
      (node (ref "C6") (pin "2") (pinfunction "2_2") (pintype "passive"))
      (node (ref "C8") (pin "2") (pinfunction "2_2") (pintype "passive"))
      (node (ref "U$1") (pin "4") (pinfunction "V-_4") (pintype "power_in"))
      (node (ref "U$10") (pin "10") (pinfunction "-VO_10") (pintype "power_in"))
      (node (ref "U$10") (pin "5") (pinfunction "-VO_5") (pintype "power_in"))
      (node (ref "U$12") (pin "4") (pinfunction "V-_4") (pintype "power_in"))
      (node (ref "U$15") (pin "4") (pinfunction "V-_4") (pintype "power_in"))
      (node (ref "U$18") (pin "4") (pinfunction "V-_4") (pintype "power_in"))
      (node (ref "U$21") (pin "4") (pinfunction "V-_4") (pintype "power_in"))
      (node (ref "U$24") (pin "4") (pinfunction "V-_4") (pintype "power_in"))
      (node (ref "U$4") (pin "4") (pinfunction "V-_4") (pintype "power_in"))
      (node (ref "U$7") (pin "4") (pinfunction "V-_4") (pintype "power_in"))
    )
    (net (code "79") (name "unconnected-(VR1-CW-Pad3)") (class "Default")
      (node (ref "VR1") (pin "3") (pinfunction "CW_3") (pintype "passive"))
    )
    (net (code "80") (name "unconnected-(VR3-CW-Pad3)") (class "Default")
      (node (ref "VR3") (pin "3") (pinfunction "CW_3") (pintype "passive"))
    )
    (net (code "81") (name "unconnected-(VR5-CW-Pad3)") (class "Default")
      (node (ref "VR5") (pin "3") (pinfunction "CW_3") (pintype "passive"))
    )
    (net (code "82") (name "unconnected-(VR7-CW-Pad3)") (class "Default")
      (node (ref "VR7") (pin "3") (pinfunction "CW_3") (pintype "passive"))
    )
    (net (code "83") (name "unconnected-(VR9-CW-Pad3)") (class "Default")
      (node (ref "VR9") (pin "3") (pinfunction "CW_3") (pintype "passive"))
    )
    (net (code "84") (name "unconnected-(VR11-CW-Pad3)") (class "Default")
      (node (ref "VR11") (pin "3") (pinfunction "CW_3") (pintype "passive"))
    )
    (net (code "85") (name "unconnected-(VR13-CW-Pad3)") (class "Default")
      (node (ref "VR13") (pin "3") (pinfunction "CW_3") (pintype "passive"))
    )
    (net (code "86") (name "unconnected-(VR15-CW-Pad3)") (class "Default")
      (node (ref "VR15") (pin "3") (pinfunction "CW_3") (pintype "passive"))
    )
  )
)
